# schematic.net
KiCad netlist of a schematic drawn in Altium Designer
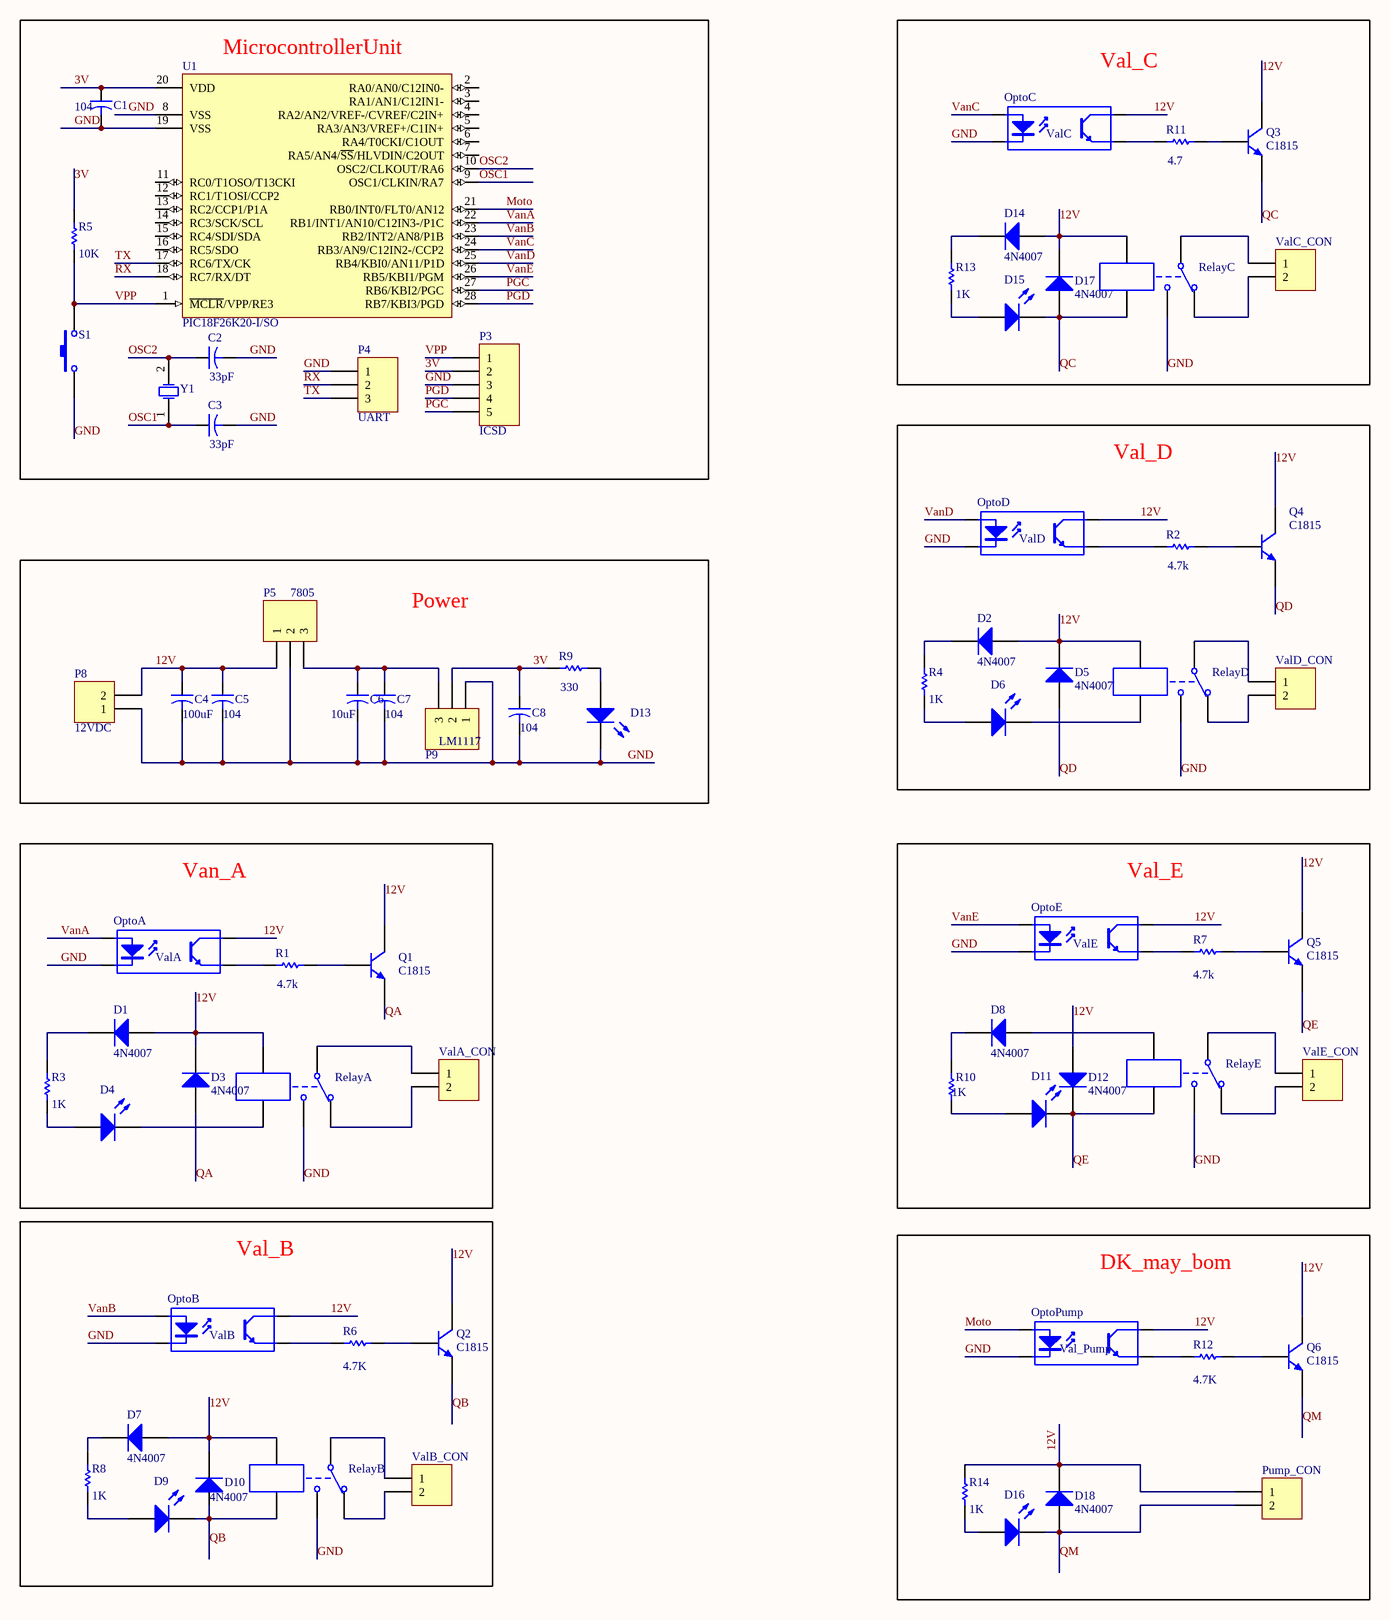
[diagram p0: schematic.SchDoc]

(export (version "E")
  (design (tool "Eeschema 10.0.6"))
  (components
    (comp (ref "C1")
      (value "104")
      (footprint "CN1")
      (description "Capacitor")
      (fields (field (name "Comment") "Cap2") (field (name "PUBLISHER") "Altium Limited"))
      (libsource (lib "Miscellaneous Devices") (part "Cap2"))
    )
    (comp (ref "C2")
      (value "33pF")
      (footprint "CN1")
      (description "Capacitor")
      (fields (field (name "Comment") "Cap2") (field (name "PUBLISHER") "Altium Limited"))
      (libsource (lib "Miscellaneous Devices") (part "Cap2"))
    )
    (comp (ref "C3")
      (value "33pF")
      (footprint "CN1")
      (description "Capacitor")
      (fields (field (name "Comment") "Cap2") (field (name "PUBLISHER") "Altium Limited"))
      (libsource (lib "Miscellaneous Devices") (part "Cap2"))
    )
    (comp (ref "C4")
      (value "100uF")
      (footprint "CP1.5/2.5")
      (description "Capacitor")
      (fields (field (name "Comment") "Cap2") (field (name "PUBLISHER") "Altium Limited"))
      (libsource (lib "Miscellaneous Devices") (part "Cap2"))
    )
    (comp (ref "C5")
      (value "104")
      (footprint "CN1")
      (description "Capacitor")
      (fields (field (name "Comment") "Cap2") (field (name "PUBLISHER") "Altium Limited"))
      (libsource (lib "Miscellaneous Devices") (part "Cap2"))
    )
    (comp (ref "C6")
      (value "10uF")
      (footprint "CP1/2")
      (description "Capacitor")
      (fields (field (name "Comment") "Cap2") (field (name "PUBLISHER") "Altium Limited"))
      (libsource (lib "Miscellaneous Devices") (part "Cap2"))
    )
    (comp (ref "C7")
      (value "104")
      (footprint "CN1")
      (description "Capacitor")
      (fields (field (name "Comment") "Cap2") (field (name "PUBLISHER") "Altium Limited"))
      (libsource (lib "Miscellaneous Devices") (part "Cap2"))
    )
    (comp (ref "C8")
      (value "104")
      (footprint "CN1")
      (description "Capacitor")
      (fields (field (name "Comment") "Cap2") (field (name "PUBLISHER") "Altium Limited"))
      (libsource (lib "Miscellaneous Devices") (part "Cap2"))
    )
    (comp (ref "D1")
      (value "4N4007")
      (footprint "D2A")
      (description "1 Amp General Purpose Rectifier")
      (fields (field (name "PUBLISHER") "Altium Limited"))
      (libsource (lib "Miscellaneous Devices") (part "Diode 1N4007"))
    )
    (comp (ref "D2")
      (value "4N4007")
      (footprint "D2A")
      (description "1 Amp General Purpose Rectifier")
      (fields (field (name "PUBLISHER") "Altium Limited"))
      (libsource (lib "Miscellaneous Devices") (part "Diode 1N4007"))
    )
    (comp (ref "D3")
      (value "4N4007")
      (footprint "D2A")
      (description "1 Amp General Purpose Rectifier")
      (fields (field (name "PUBLISHER") "Altium Limited"))
      (libsource (lib "Miscellaneous Devices") (part "Diode 1N4007"))
    )
    (comp (ref "D4")
      (value "LED1")
      (footprint "LED-5TRED")
      (description "Typical RED GaAs LED")
      (fields (field (name "PUBLISHER") "Altium Limited"))
      (libsource (lib "Miscellaneous Devices") (part "LED1"))
    )
    (comp (ref "D5")
      (value "4N4007")
      (footprint "D2A")
      (description "1 Amp General Purpose Rectifier")
      (fields (field (name "PUBLISHER") "Altium Limited"))
      (libsource (lib "Miscellaneous Devices") (part "Diode 1N4007"))
    )
    (comp (ref "D6")
      (value "LED1")
      (footprint "LED-5TRED")
      (description "Typical RED GaAs LED")
      (fields (field (name "PUBLISHER") "Altium Limited"))
      (libsource (lib "Miscellaneous Devices") (part "LED1"))
    )
    (comp (ref "D7")
      (value "4N4007")
      (footprint "D2A")
      (description "1 Amp General Purpose Rectifier")
      (fields (field (name "PUBLISHER") "Altium Limited"))
      (libsource (lib "Miscellaneous Devices") (part "Diode 1N4007"))
    )
    (comp (ref "D8")
      (value "4N4007")
      (footprint "D2A")
      (description "1 Amp General Purpose Rectifier")
      (fields (field (name "PUBLISHER") "Altium Limited"))
      (libsource (lib "Miscellaneous Devices") (part "Diode 1N4007"))
    )
    (comp (ref "D9")
      (value "LED1")
      (footprint "LED-5TRED")
      (description "Typical RED GaAs LED")
      (fields (field (name "PUBLISHER") "Altium Limited"))
      (libsource (lib "Miscellaneous Devices") (part "LED1"))
    )
    (comp (ref "D10")
      (value "4N4007")
      (footprint "D2A")
      (description "1 Amp General Purpose Rectifier")
      (fields (field (name "PUBLISHER") "Altium Limited"))
      (libsource (lib "Miscellaneous Devices") (part "Diode 1N4007"))
    )
    (comp (ref "D11")
      (value "LED1")
      (footprint "LED-5TRED")
      (description "Typical RED GaAs LED")
      (fields (field (name "PUBLISHER") "Altium Limited"))
      (libsource (lib "Miscellaneous Devices") (part "LED1"))
    )
    (comp (ref "D12")
      (value "4N4007")
      (footprint "D2A")
      (description "1 Amp General Purpose Rectifier")
      (fields (field (name "PUBLISHER") "Altium Limited"))
      (libsource (lib "Miscellaneous Devices") (part "Diode 1N4007"))
    )
    (comp (ref "D13")
      (value "LED1")
      (footprint "LED-5TRED")
      (description "Typical RED GaAs LED")
      (fields (field (name "PUBLISHER") "Altium Limited"))
      (libsource (lib "Miscellaneous Devices") (part "LED1"))
    )
    (comp (ref "D14")
      (value "4N4007")
      (footprint "D2A")
      (description "1 Amp General Purpose Rectifier")
      (fields (field (name "PUBLISHER") "Altium Limited"))
      (libsource (lib "Miscellaneous Devices") (part "Diode 1N4007"))
    )
    (comp (ref "D15")
      (value "LED1")
      (footprint "LED-5TRED")
      (description "Typical RED GaAs LED")
      (fields (field (name "PUBLISHER") "Altium Limited"))
      (libsource (lib "Miscellaneous Devices") (part "LED1"))
    )
    (comp (ref "D16")
      (value "LED1")
      (footprint "LED-5TRED")
      (description "Typical RED GaAs LED")
      (fields (field (name "PUBLISHER") "Altium Limited"))
      (libsource (lib "Miscellaneous Devices") (part "LED1"))
    )
    (comp (ref "D17")
      (value "4N4007")
      (footprint "D2A")
      (description "1 Amp General Purpose Rectifier")
      (fields (field (name "PUBLISHER") "Altium Limited"))
      (libsource (lib "Miscellaneous Devices") (part "Diode 1N4007"))
    )
    (comp (ref "D18")
      (value "4N4007")
      (footprint "D2A")
      (description "1 Amp General Purpose Rectifier")
      (fields (field (name "PUBLISHER") "Altium Limited"))
      (libsource (lib "Miscellaneous Devices") (part "Diode 1N4007"))
    )
    (comp (ref "OptoA")
      (value "ValA")
      (footprint "DIP4/W0.3")
      (description "4-Pin Phototransistor Optocoupler")
      (fields (field (name "PUBLISHER") "Altium Limited"))
      (libsource (lib "Miscellaneous Devices") (part "Optoisolator1"))
    )
    (comp (ref "OptoB")
      (value "ValB")
      (footprint "DIP4/W0.3")
      (description "4-Pin Phototransistor Optocoupler")
      (fields (field (name "PUBLISHER") "Altium Limited"))
      (libsource (lib "Miscellaneous Devices") (part "Optoisolator1"))
    )
    (comp (ref "OptoC")
      (value "ValC")
      (footprint "DIP4/W0.3")
      (description "4-Pin Phototransistor Optocoupler")
      (fields (field (name "PUBLISHER") "Altium Limited"))
      (libsource (lib "Miscellaneous Devices") (part "Optoisolator1"))
    )
    (comp (ref "OptoD")
      (value "ValD")
      (footprint "DIP4/W0.3")
      (description "4-Pin Phototransistor Optocoupler")
      (fields (field (name "PUBLISHER") "Altium Limited"))
      (libsource (lib "Miscellaneous Devices") (part "Optoisolator1"))
    )
    (comp (ref "OptoE")
      (value "ValE")
      (footprint "DIP4/W0.3")
      (description "4-Pin Phototransistor Optocoupler")
      (fields (field (name "PUBLISHER") "Altium Limited"))
      (libsource (lib "Miscellaneous Devices") (part "Optoisolator1"))
    )
    (comp (ref "OptoPump")
      (value "Val_Pump")
      (footprint "DIP4/W0.3")
      (description "4-Pin Phototransistor Optocoupler")
      (fields (field (name "PUBLISHER") "Altium Limited"))
      (libsource (lib "Miscellaneous Devices") (part "Optoisolator1"))
    )
    (comp (ref "P3")
      (value "ICSD")
      (footprint "JP5")
      (description "Header, 5-Pin, Right Angle")
      (fields (field (name "PUBLISHER") "Altium Limited"))
      (libsource (lib "Miscellaneous Connectors") (part "Header 5H"))
    )
    (comp (ref "P4")
      (value "UART")
      (footprint "JP3")
      (description "Header, 3-Pin, Right Angle")
      (fields (field (name "PUBLISHER") "Altium Limited"))
      (libsource (lib "Miscellaneous Connectors") (part "Header 3H"))
    )
    (comp (ref "P5")
      (value "7805")
      (footprint "JP3")
      (description "Header, 3-Pin, Right Angle")
      (fields (field (name "PUBLISHER") "Altium Limited"))
      (libsource (lib "") (part "Header 3H_2"))
    )
    (comp (ref "P8")
      (value "12VDC")
      (footprint "DC-IN")
      (description "Header, 2-Pin")
      (fields (field (name "PUBLISHER") "Altium Limited"))
      (libsource (lib "") (part "Header 2_1"))
    )
    (comp (ref "P9")
      (value "LM1117")
      (footprint "JP3")
      (description "Header, 3-Pin, Right Angle")
      (fields (field (name "PUBLISHER") "Altium Limited"))
      (libsource (lib "") (part "Header 3H_1"))
    )
    (comp (ref "Pump_CON")
      (value "Header 2")
      (footprint "CON2")
      (description "Header, 2-Pin")
      (fields (field (name "PUBLISHER") "Altium Limited"))
      (libsource (lib "Miscellaneous Connectors") (part "Header 2"))
    )
    (comp (ref "Q1")
      (value "C1815")
      (footprint "QTO-92")
      (description "NPN General Purpose Amplifier")
      (fields (field (name "PUBLISHER") "Altium Limited"))
      (libsource (lib "Miscellaneous Devices") (part "2N3904"))
    )
    (comp (ref "Q2")
      (value "C1815")
      (footprint "QTO-92")
      (description "NPN General Purpose Amplifier")
      (fields (field (name "PUBLISHER") "Altium Limited"))
      (libsource (lib "Miscellaneous Devices") (part "2N3904"))
    )
    (comp (ref "Q3")
      (value "C1815")
      (footprint "QTO-92")
      (description "NPN General Purpose Amplifier")
      (fields (field (name "PUBLISHER") "Altium Limited"))
      (libsource (lib "Miscellaneous Devices") (part "2N3904"))
    )
    (comp (ref "Q4")
      (value "C1815")
      (footprint "QTO-92")
      (description "NPN General Purpose Amplifier")
      (fields (field (name "PUBLISHER") "Altium Limited"))
      (libsource (lib "Miscellaneous Devices") (part "2N3904"))
    )
    (comp (ref "Q5")
      (value "C1815")
      (footprint "QTO-92")
      (description "NPN General Purpose Amplifier")
      (fields (field (name "PUBLISHER") "Altium Limited"))
      (libsource (lib "Miscellaneous Devices") (part "2N3904"))
    )
    (comp (ref "Q6")
      (value "C1815")
      (footprint "QTO-92")
      (description "NPN General Purpose Amplifier")
      (fields (field (name "PUBLISHER") "Altium Limited"))
      (libsource (lib "Miscellaneous Devices") (part "2N3904"))
    )
    (comp (ref "R1")
      (value "4.7k")
      (footprint "R1/4W")
      (description "Resistor")
      (fields (field (name "Comment") "Res1") (field (name "PUBLISHER") "Altium Limited"))
      (libsource (lib "Miscellaneous Devices") (part "Res1"))
    )
    (comp (ref "R2")
      (value "4.7k")
      (footprint "R1/4W")
      (description "Resistor")
      (fields (field (name "PUBLISHER") "Altium Limited"))
      (libsource (lib "Miscellaneous Devices") (part "Res1"))
    )
    (comp (ref "R3")
      (value "1K")
      (footprint "R1/4W")
      (description "Resistor")
      (fields (field (name "Comment") "Res1") (field (name "PUBLISHER") "Altium Limited"))
      (libsource (lib "Miscellaneous Devices") (part "Res1"))
    )
    (comp (ref "R4")
      (value "1K")
      (footprint "R1/4W")
      (description "Resistor")
      (fields (field (name "Comment") "Res1") (field (name "PUBLISHER") "Altium Limited"))
      (libsource (lib "Miscellaneous Devices") (part "Res1"))
    )
    (comp (ref "R5")
      (value "10K")
      (footprint "R1/4W")
      (description "Resistor")
      (fields (field (name "Comment") "Res1") (field (name "PUBLISHER") "Altium Limited"))
      (libsource (lib "Miscellaneous Devices") (part "Res1"))
    )
    (comp (ref "R6")
      (value "4.7K")
      (footprint "R1/4W")
      (description "Resistor")
      (fields (field (name "Comment") "Res1") (field (name "PUBLISHER") "Altium Limited"))
      (libsource (lib "Miscellaneous Devices") (part "Res1"))
    )
    (comp (ref "R7")
      (value "4.7k")
      (footprint "R1/4W")
      (description "Resistor")
      (fields (field (name "Comment") "Res1") (field (name "PUBLISHER") "Altium Limited"))
      (libsource (lib "Miscellaneous Devices") (part "Res1"))
    )
    (comp (ref "R8")
      (value "1K")
      (footprint "R1/4W")
      (description "Resistor")
      (fields (field (name "Comment") "Res1") (field (name "PUBLISHER") "Altium Limited"))
      (libsource (lib "Miscellaneous Devices") (part "Res1"))
    )
    (comp (ref "R9")
      (value "330")
      (footprint "R1/4W")
      (description "Resistor")
      (fields (field (name "Comment") "Res1") (field (name "PUBLISHER") "Altium Limited"))
      (libsource (lib "Miscellaneous Devices") (part "Res1"))
    )
    (comp (ref "R10")
      (value "1K")
      (footprint "R1/4W")
      (description "Resistor")
      (fields (field (name "Comment") "Res1") (field (name "PUBLISHER") "Altium Limited"))
      (libsource (lib "Miscellaneous Devices") (part "Res1"))
    )
    (comp (ref "R11")
      (value "4.7")
      (footprint "R1/4W")
      (description "Resistor")
      (fields (field (name "Comment") "Res1") (field (name "PUBLISHER") "Altium Limited"))
      (libsource (lib "Miscellaneous Devices") (part "Res1"))
    )
    (comp (ref "R12")
      (value "4.7K")
      (footprint "R1/4W")
      (description "Resistor")
      (fields (field (name "Comment") "Res1") (field (name "PUBLISHER") "Altium Limited"))
      (libsource (lib "Miscellaneous Devices") (part "Res1"))
    )
    (comp (ref "R13")
      (value "1K")
      (footprint "R1/4W")
      (description "Resistor")
      (fields (field (name "Comment") "Res1") (field (name "PUBLISHER") "Altium Limited"))
      (libsource (lib "Miscellaneous Devices") (part "Res1"))
    )
    (comp (ref "R14")
      (value "1K")
      (footprint "R1/4W")
      (description "Resistor")
      (fields (field (name "Comment") "Res1") (field (name "PUBLISHER") "Altium Limited"))
      (libsource (lib "Miscellaneous Devices") (part "Res1"))
    )
    (comp (ref "RelayA")
      (value "Relay-SPDT")
      (footprint "RL_SPDT_10A")
      (description "Single-Pole Dual-Throw Relay")
      (fields (field (name "PUBLISHER") "Altium Limited"))
      (libsource (lib "Miscellaneous Devices") (part "Relay-SPDT"))
    )
    (comp (ref "RelayB")
      (value "Relay-SPDT")
      (footprint "RL_SPDT_10A")
      (description "Single-Pole Dual-Throw Relay")
      (fields (field (name "PUBLISHER") "Altium Limited"))
      (libsource (lib "Miscellaneous Devices") (part "Relay-SPDT"))
    )
    (comp (ref "RelayC")
      (value "Relay-SPDT")
      (footprint "RL_SPDT_10A")
      (description "Single-Pole Dual-Throw Relay")
      (fields (field (name "PUBLISHER") "Altium Limited"))
      (libsource (lib "Miscellaneous Devices") (part "Relay-SPDT"))
    )
    (comp (ref "RelayD")
      (value "Relay-SPDT")
      (footprint "RL_SPDT_10A")
      (description "Single-Pole Dual-Throw Relay")
      (fields (field (name "PUBLISHER") "Altium Limited"))
      (libsource (lib "Miscellaneous Devices") (part "Relay-SPDT"))
    )
    (comp (ref "RelayE")
      (value "Relay-SPDT")
      (footprint "RL_SPDT_10A")
      (description "Single-Pole Dual-Throw Relay")
      (fields (field (name "PUBLISHER") "Altium Limited"))
      (libsource (lib "Miscellaneous Devices") (part "Relay-SPDT"))
    )
    (comp (ref "S1")
      (value "SW-PB")
      (footprint "SW2")
      (description "Switch")
      (fields (field (name "PUBLISHER") "Altium Limited"))
      (libsource (lib "Miscellaneous Devices") (part "SW-PB"))
    )
    (comp (ref "U1")
      (value "PIC18F26K20-I/SO")
      (footprint "SOP_28M_127")
      (fields (field (name "PUBLISHER") "Altium Limited"))
      (libsource (lib "Microchip Microcontroller 8-Bit PIC18") (part "PIC18F26K20-I/SO"))
    )
    (comp (ref "ValA_CON")
      (value "Header 2")
      (footprint "CON2")
      (description "Header, 2-Pin")
      (fields (field (name "PUBLISHER") "Altium Limited"))
      (libsource (lib "Miscellaneous Connectors") (part "Header 2"))
    )
    (comp (ref "ValB_CON")
      (value "Header 2")
      (footprint "CON2")
      (description "Header, 2-Pin")
      (fields (field (name "PUBLISHER") "Altium Limited"))
      (libsource (lib "Miscellaneous Connectors") (part "Header 2"))
    )
    (comp (ref "ValC_CON")
      (value "Header 2")
      (footprint "CON2")
      (description "Header, 2-Pin")
      (fields (field (name "PUBLISHER") "Altium Limited"))
      (libsource (lib "Miscellaneous Connectors") (part "Header 2"))
    )
    (comp (ref "ValD_CON")
      (value "Header 2")
      (footprint "CON2")
      (description "Header, 2-Pin")
      (fields (field (name "PUBLISHER") "Altium Limited"))
      (libsource (lib "Miscellaneous Connectors") (part "Header 2"))
    )
    (comp (ref "ValE_CON")
      (value "Header 2")
      (footprint "CON2")
      (description "Header, 2-Pin")
      (fields (field (name "PUBLISHER") "Altium Limited"))
      (libsource (lib "Miscellaneous Connectors") (part "Header 2"))
    )
    (comp (ref "Y1")
      (value "8Mhz")
      (footprint "XT2")
      (description "Crystal Oscillator")
      (fields (field (name "PUBLISHER") "Altium Limited"))
      (libsource (lib "Miscellaneous Devices") (part "XTAL"))
    )
  )
  (nets
    (net (code "1") (name "/3V") (class "Default")
      (node (ref "C1") (pin "1") (pinfunction "1_1") (pintype "passive"))
      (node (ref "C8") (pin "1") (pinfunction "1_1") (pintype "passive"))
      (node (ref "P3") (pin "2") (pinfunction "2_2") (pintype "passive"))
      (node (ref "P9") (pin "2") (pinfunction "2_2") (pintype "passive"))
      (node (ref "R5") (pin "2") (pinfunction "2_2") (pintype "passive"))
      (node (ref "R9") (pin "1") (pinfunction "1_1") (pintype "passive"))
      (node (ref "U1") (pin "20") (pinfunction "VDD_20") (pintype "power_in"))
    )
    (net (code "2") (name "/12V") (class "Default")
      (node (ref "C4") (pin "1") (pinfunction "1_1") (pintype "passive"))
      (node (ref "C5") (pin "1") (pinfunction "1_1") (pintype "passive"))
      (node (ref "D1") (pin "1") (pinfunction "A_1") (pintype "passive"))
      (node (ref "D10") (pin "2") (pinfunction "K_2") (pintype "passive"))
      (node (ref "D12") (pin "1") (pinfunction "A_1") (pintype "passive"))
      (node (ref "D14") (pin "1") (pinfunction "A_1") (pintype "passive"))
      (node (ref "D17") (pin "2") (pinfunction "K_2") (pintype "passive"))
      (node (ref "D18") (pin "2") (pinfunction "K_2") (pintype "passive"))
      (node (ref "D2") (pin "1") (pinfunction "A_1") (pintype "passive"))
      (node (ref "D3") (pin "2") (pinfunction "K_2") (pintype "passive"))
      (node (ref "D5") (pin "2") (pinfunction "K_2") (pintype "passive"))
      (node (ref "D7") (pin "1") (pinfunction "A_1") (pintype "passive"))
      (node (ref "OptoA") (pin "4") (pinfunction "C_4") (pintype "passive"))
      (node (ref "OptoB") (pin "4") (pinfunction "C_4") (pintype "passive"))
      (node (ref "OptoC") (pin "4") (pinfunction "C_4") (pintype "passive"))
      (node (ref "OptoD") (pin "4") (pinfunction "C_4") (pintype "passive"))
      (node (ref "OptoE") (pin "4") (pinfunction "C_4") (pintype "passive"))
      (node (ref "OptoPump") (pin "4") (pinfunction "C_4") (pintype "passive"))
      (node (ref "P5") (pin "1") (pinfunction "1_1") (pintype "passive"))
      (node (ref "P8") (pin "2") (pinfunction "2_2") (pintype "passive"))
      (node (ref "Pump_CON") (pin "1") (pinfunction "1_1") (pintype "passive"))
      (node (ref "Q1") (pin "3") (pinfunction "C_3") (pintype "passive"))
      (node (ref "Q2") (pin "3") (pinfunction "C_3") (pintype "passive"))
      (node (ref "Q3") (pin "3") (pinfunction "C_3") (pintype "passive"))
      (node (ref "Q4") (pin "3") (pinfunction "C_3") (pintype "passive"))
      (node (ref "Q5") (pin "3") (pinfunction "C_3") (pintype "passive"))
      (node (ref "Q6") (pin "3") (pinfunction "C_3") (pintype "passive"))
      (node (ref "R14") (pin "1") (pinfunction "1_1") (pintype "passive"))
      (node (ref "RelayA") (pin "4") (pinfunction "4_4") (pintype "passive"))
      (node (ref "RelayB") (pin "4") (pinfunction "4_4") (pintype "passive"))
      (node (ref "RelayC") (pin "4") (pinfunction "4_4") (pintype "passive"))
      (node (ref "RelayD") (pin "4") (pinfunction "4_4") (pintype "passive"))
    )
    (net (code "3") (name "/GND") (class "Default")
      (node (ref "C1") (pin "2") (pinfunction "2_2") (pintype "passive"))
      (node (ref "C2") (pin "2") (pinfunction "2_2") (pintype "passive"))
      (node (ref "C3") (pin "2") (pinfunction "2_2") (pintype "passive"))
      (node (ref "C4") (pin "2") (pinfunction "2_2") (pintype "passive"))
      (node (ref "C5") (pin "2") (pinfunction "2_2") (pintype "passive"))
      (node (ref "C6") (pin "2") (pinfunction "2_2") (pintype "passive"))
      (node (ref "C7") (pin "2") (pinfunction "2_2") (pintype "passive"))
      (node (ref "C8") (pin "2") (pinfunction "2_2") (pintype "passive"))
      (node (ref "D13") (pin "2") (pinfunction "K_2") (pintype "passive"))
      (node (ref "OptoA") (pin "2") (pinfunction "K_2") (pintype "passive"))
      (node (ref "OptoB") (pin "2") (pinfunction "K_2") (pintype "passive"))
      (node (ref "OptoC") (pin "2") (pinfunction "K_2") (pintype "passive"))
      (node (ref "OptoD") (pin "2") (pinfunction "K_2") (pintype "passive"))
      (node (ref "OptoE") (pin "2") (pinfunction "K_2") (pintype "passive"))
      (node (ref "OptoPump") (pin "2") (pinfunction "K_2") (pintype "passive"))
      (node (ref "P3") (pin "3") (pinfunction "3_3") (pintype "passive"))
      (node (ref "P4") (pin "1") (pinfunction "1_1") (pintype "passive"))
      (node (ref "P5") (pin "2") (pinfunction "2_2") (pintype "passive"))
      (node (ref "P8") (pin "1") (pinfunction "1_1") (pintype "passive"))
      (node (ref "P9") (pin "1") (pinfunction "1_1") (pintype "passive"))
      (node (ref "RelayA") (pin "3") (pinfunction "3_3") (pintype "passive"))
      (node (ref "RelayB") (pin "3") (pinfunction "3_3") (pintype "passive"))
      (node (ref "RelayC") (pin "3") (pinfunction "3_3") (pintype "passive"))
      (node (ref "RelayD") (pin "3") (pinfunction "3_3") (pintype "passive"))
      (node (ref "RelayE") (pin "3") (pinfunction "3_3") (pintype "passive"))
      (node (ref "S1") (pin "1") (pinfunction "1_1") (pintype "passive"))
      (node (ref "U1") (pin "19") (pinfunction "VSS_19") (pintype "power_in"))
      (node (ref "U1") (pin "8") (pinfunction "VSS_8") (pintype "power_in"))
    )
    (net (code "4") (name "/Moto") (class "Default")
      (node (ref "OptoPump") (pin "1") (pinfunction "A_1") (pintype "passive"))
      (node (ref "U1") (pin "21") (pinfunction "RB0/INT0/FLT0/AN12_21") (pintype "bidirectional"))
    )
    (net (code "5") (name "/OSC1") (class "Default")
      (node (ref "C3") (pin "1") (pinfunction "1_1") (pintype "passive"))
      (node (ref "U1") (pin "9") (pinfunction "OSC1/CLKIN/RA7_9") (pintype "bidirectional"))
      (node (ref "Y1") (pin "1") (pinfunction "OSC1_1") (pintype "passive"))
    )
    (net (code "6") (name "/OSC2") (class "Default")
      (node (ref "C2") (pin "1") (pinfunction "1_1") (pintype "passive"))
      (node (ref "U1") (pin "10") (pinfunction "OSC2/CLKOUT/RA6_10") (pintype "bidirectional"))
      (node (ref "Y1") (pin "2") (pinfunction "OSC2_2") (pintype "passive"))
    )
    (net (code "7") (name "/PGC") (class "Default")
      (node (ref "P3") (pin "5") (pinfunction "5_5") (pintype "passive"))
      (node (ref "U1") (pin "27") (pinfunction "RB6/KBI2/PGC_27") (pintype "bidirectional"))
    )
    (net (code "8") (name "/PGD") (class "Default")
      (node (ref "P3") (pin "4") (pinfunction "4_4") (pintype "passive"))
      (node (ref "U1") (pin "28") (pinfunction "RB7/KBI3/PGD_28") (pintype "bidirectional"))
    )
    (net (code "9") (name "/QA") (class "Default")
      (node (ref "D3") (pin "1") (pinfunction "A_1") (pintype "passive"))
      (node (ref "Q1") (pin "1") (pinfunction "E_1") (pintype "passive"))
    )
    (net (code "10") (name "/QB") (class "Default")
      (node (ref "D10") (pin "1") (pinfunction "A_1") (pintype "passive"))
      (node (ref "D9") (pin "2") (pinfunction "K_2") (pintype "passive"))
      (node (ref "Q2") (pin "1") (pinfunction "E_1") (pintype "passive"))
      (node (ref "RelayB") (pin "5") (pinfunction "5_5") (pintype "passive"))
    )
    (net (code "11") (name "/QC") (class "Default")
      (node (ref "D15") (pin "2") (pinfunction "K_2") (pintype "passive"))
      (node (ref "D17") (pin "1") (pinfunction "A_1") (pintype "passive"))
      (node (ref "Q3") (pin "1") (pinfunction "E_1") (pintype "passive"))
      (node (ref "RelayC") (pin "5") (pinfunction "5_5") (pintype "passive"))
    )
    (net (code "12") (name "/QD") (class "Default")
      (node (ref "D5") (pin "1") (pinfunction "A_1") (pintype "passive"))
      (node (ref "Q4") (pin "1") (pinfunction "E_1") (pintype "passive"))
    )
    (net (code "13") (name "/QE") (class "Default")
      (node (ref "D11") (pin "2") (pinfunction "K_2") (pintype "passive"))
      (node (ref "D12") (pin "2") (pinfunction "K_2") (pintype "passive"))
      (node (ref "Q5") (pin "1") (pinfunction "E_1") (pintype "passive"))
      (node (ref "RelayE") (pin "5") (pinfunction "5_5") (pintype "passive"))
    )
    (net (code "14") (name "/QM") (class "Default")
      (node (ref "D16") (pin "2") (pinfunction "K_2") (pintype "passive"))
      (node (ref "D18") (pin "1") (pinfunction "A_1") (pintype "passive"))
      (node (ref "Pump_CON") (pin "2") (pinfunction "2_2") (pintype "passive"))
      (node (ref "Q6") (pin "1") (pinfunction "E_1") (pintype "passive"))
    )
    (net (code "15") (name "/RX") (class "Default")
      (node (ref "P4") (pin "2") (pinfunction "2_2") (pintype "passive"))
      (node (ref "U1") (pin "18") (pinfunction "RC7/RX/DT_18") (pintype "bidirectional"))
    )
    (net (code "16") (name "/TX") (class "Default")
      (node (ref "P4") (pin "3") (pinfunction "3_3") (pintype "passive"))
      (node (ref "U1") (pin "17") (pinfunction "RC6/TX/CK_17") (pintype "bidirectional"))
    )
    (net (code "17") (name "/VPP") (class "Default")
      (node (ref "P3") (pin "1") (pinfunction "1_1") (pintype "passive"))
      (node (ref "R5") (pin "1") (pinfunction "1_1") (pintype "passive"))
      (node (ref "S1") (pin "2") (pinfunction "2_2") (pintype "passive"))
      (node (ref "U1") (pin "1") (pinfunction "~{MCLR}/VPP/RE3_1") (pintype "input"))
    )
    (net (code "18") (name "/VanA") (class "Default")
      (node (ref "OptoA") (pin "1") (pinfunction "A_1") (pintype "passive"))
      (node (ref "U1") (pin "22") (pinfunction "RB1/INT1/AN10/C12IN3-/P1C_22") (pintype "bidirectional"))
    )
    (net (code "19") (name "/VanB") (class "Default")
      (node (ref "OptoB") (pin "1") (pinfunction "A_1") (pintype "passive"))
      (node (ref "U1") (pin "23") (pinfunction "RB2/INT2/AN8/P1B_23") (pintype "bidirectional"))
    )
    (net (code "20") (name "/VanC") (class "Default")
      (node (ref "OptoC") (pin "1") (pinfunction "A_1") (pintype "passive"))
      (node (ref "U1") (pin "24") (pinfunction "RB3/AN9/C12IN2-/CCP2_24") (pintype "bidirectional"))
    )
    (net (code "21") (name "/VanD") (class "Default")
      (node (ref "OptoD") (pin "1") (pinfunction "A_1") (pintype "passive"))
      (node (ref "U1") (pin "25") (pinfunction "RB4/KBI0/AN11/P1D_25") (pintype "bidirectional"))
    )
    (net (code "22") (name "/VanE") (class "Default")
      (node (ref "OptoE") (pin "1") (pinfunction "A_1") (pintype "passive"))
      (node (ref "U1") (pin "26") (pinfunction "RB5/KBI1/PGM_26") (pintype "bidirectional"))
    )
    (net (code "23") (name "Net-(C6-Pad1)") (class "Default")
      (node (ref "C6") (pin "1") (pinfunction "1_1") (pintype "passive"))
      (node (ref "C7") (pin "1") (pinfunction "1_1") (pintype "passive"))
      (node (ref "P5") (pin "3") (pinfunction "3_3") (pintype "passive"))
      (node (ref "P9") (pin "3") (pinfunction "3_3") (pintype "passive"))
    )
    (net (code "24") (name "Net-(D1-K)") (class "Default")
      (node (ref "D1") (pin "2") (pinfunction "K_2") (pintype "passive"))
      (node (ref "R3") (pin "1") (pinfunction "1_1") (pintype "passive"))
    )
    (net (code "25") (name "Net-(D2-K)") (class "Default")
      (node (ref "D2") (pin "2") (pinfunction "K_2") (pintype "passive"))
      (node (ref "R4") (pin "1") (pinfunction "1_1") (pintype "passive"))
    )
    (net (code "26") (name "Net-(D4-A)") (class "Default")
      (node (ref "D4") (pin "1") (pinfunction "A_1") (pintype "passive"))
      (node (ref "R3") (pin "2") (pinfunction "2_2") (pintype "passive"))
    )
    (net (code "27") (name "Net-(D4-K)") (class "Default")
      (node (ref "D4") (pin "2") (pinfunction "K_2") (pintype "passive"))
      (node (ref "RelayA") (pin "5") (pinfunction "5_5") (pintype "passive"))
    )
    (net (code "28") (name "Net-(D6-A)") (class "Default")
      (node (ref "D6") (pin "1") (pinfunction "A_1") (pintype "passive"))
      (node (ref "R4") (pin "2") (pinfunction "2_2") (pintype "passive"))
    )
    (net (code "29") (name "Net-(D6-K)") (class "Default")
      (node (ref "D6") (pin "2") (pinfunction "K_2") (pintype "passive"))
      (node (ref "RelayD") (pin "5") (pinfunction "5_5") (pintype "passive"))
    )
    (net (code "30") (name "Net-(D7-K)") (class "Default")
      (node (ref "D7") (pin "2") (pinfunction "K_2") (pintype "passive"))
      (node (ref "R8") (pin "1") (pinfunction "1_1") (pintype "passive"))
    )
    (net (code "31") (name "Net-(D8-A)") (class "Default")
      (node (ref "D8") (pin "1") (pinfunction "A_1") (pintype "passive"))
      (node (ref "RelayE") (pin "4") (pinfunction "4_4") (pintype "passive"))
    )
    (net (code "32") (name "Net-(D8-K)") (class "Default")
      (node (ref "D8") (pin "2") (pinfunction "K_2") (pintype "passive"))
      (node (ref "R10") (pin "1") (pinfunction "1_1") (pintype "passive"))
    )
    (net (code "33") (name "Net-(D9-A)") (class "Default")
      (node (ref "D9") (pin "1") (pinfunction "A_1") (pintype "passive"))
      (node (ref "R8") (pin "2") (pinfunction "2_2") (pintype "passive"))
    )
    (net (code "34") (name "Net-(D11-A)") (class "Default")
      (node (ref "D11") (pin "1") (pinfunction "A_1") (pintype "passive"))
      (node (ref "R10") (pin "2") (pinfunction "2_2") (pintype "passive"))
    )
    (net (code "35") (name "Net-(D13-A)") (class "Default")
      (node (ref "D13") (pin "1") (pinfunction "A_1") (pintype "passive"))
      (node (ref "R9") (pin "2") (pinfunction "2_2") (pintype "passive"))
    )
    (net (code "36") (name "Net-(D14-K)") (class "Default")
      (node (ref "D14") (pin "2") (pinfunction "K_2") (pintype "passive"))
      (node (ref "R13") (pin "1") (pinfunction "1_1") (pintype "passive"))
    )
    (net (code "37") (name "Net-(D15-A)") (class "Default")
      (node (ref "D15") (pin "1") (pinfunction "A_1") (pintype "passive"))
      (node (ref "R13") (pin "2") (pinfunction "2_2") (pintype "passive"))
    )
    (net (code "38") (name "Net-(D16-A)") (class "Default")
      (node (ref "D16") (pin "1") (pinfunction "A_1") (pintype "passive"))
      (node (ref "R14") (pin "2") (pinfunction "2_2") (pintype "passive"))
    )
    (net (code "39") (name "Net-(OptoA-E)") (class "Default")
      (node (ref "OptoA") (pin "3") (pinfunction "E_3") (pintype "passive"))
      (node (ref "R1") (pin "1") (pinfunction "1_1") (pintype "passive"))
    )
    (net (code "40") (name "Net-(OptoB-E)") (class "Default")
      (node (ref "OptoB") (pin "3") (pinfunction "E_3") (pintype "passive"))
      (node (ref "R6") (pin "1") (pinfunction "1_1") (pintype "passive"))
    )
    (net (code "41") (name "Net-(OptoC-E)") (class "Default")
      (node (ref "OptoC") (pin "3") (pinfunction "E_3") (pintype "passive"))
      (node (ref "R11") (pin "1") (pinfunction "1_1") (pintype "passive"))
    )
    (net (code "42") (name "Net-(OptoD-E)") (class "Default")
      (node (ref "OptoD") (pin "3") (pinfunction "E_3") (pintype "passive"))
      (node (ref "R2") (pin "1") (pinfunction "1_1") (pintype "passive"))
    )
    (net (code "43") (name "Net-(OptoE-E)") (class "Default")
      (node (ref "OptoE") (pin "3") (pinfunction "E_3") (pintype "passive"))
      (node (ref "R7") (pin "1") (pinfunction "1_1") (pintype "passive"))
    )
    (net (code "44") (name "Net-(OptoPump-E)") (class "Default")
      (node (ref "OptoPump") (pin "3") (pinfunction "E_3") (pintype "passive"))
      (node (ref "R12") (pin "1") (pinfunction "1_1") (pintype "passive"))
    )
    (net (code "45") (name "Net-(Q1-B)") (class "Default")
      (node (ref "Q1") (pin "2") (pinfunction "B_2") (pintype "passive"))
      (node (ref "R1") (pin "2") (pinfunction "2_2") (pintype "passive"))
    )
    (net (code "46") (name "Net-(Q2-B)") (class "Default")
      (node (ref "Q2") (pin "2") (pinfunction "B_2") (pintype "passive"))
      (node (ref "R6") (pin "2") (pinfunction "2_2") (pintype "passive"))
    )
    (net (code "47") (name "Net-(Q3-B)") (class "Default")
      (node (ref "Q3") (pin "2") (pinfunction "B_2") (pintype "passive"))
      (node (ref "R11") (pin "2") (pinfunction "2_2") (pintype "passive"))
    )
    (net (code "48") (name "Net-(Q4-B)") (class "Default")
      (node (ref "Q4") (pin "2") (pinfunction "B_2") (pintype "passive"))
      (node (ref "R2") (pin "2") (pinfunction "2_2") (pintype "passive"))
    )
    (net (code "49") (name "Net-(Q5-B)") (class "Default")
      (node (ref "Q5") (pin "2") (pinfunction "B_2") (pintype "passive"))
      (node (ref "R7") (pin "2") (pinfunction "2_2") (pintype "passive"))
    )
    (net (code "50") (name "Net-(Q6-B)") (class "Default")
      (node (ref "Q6") (pin "2") (pinfunction "B_2") (pintype "passive"))
      (node (ref "R12") (pin "2") (pinfunction "2_2") (pintype "passive"))
    )
    (net (code "51") (name "Net-(RelayA-Pad1)") (class "Default")
      (node (ref "RelayA") (pin "1") (pinfunction "1_1") (pintype "passive"))
      (node (ref "ValA_CON") (pin "1") (pinfunction "1_1") (pintype "passive"))
    )
    (net (code "52") (name "Net-(RelayA-Pad2)") (class "Default")
      (node (ref "RelayA") (pin "2") (pinfunction "2_2") (pintype "passive"))
      (node (ref "ValA_CON") (pin "2") (pinfunction "2_2") (pintype "passive"))
    )
    (net (code "53") (name "Net-(RelayB-Pad1)") (class "Default")
      (node (ref "RelayB") (pin "1") (pinfunction "1_1") (pintype "passive"))
      (node (ref "ValB_CON") (pin "1") (pinfunction "1_1") (pintype "passive"))
    )
    (net (code "54") (name "Net-(RelayB-Pad2)") (class "Default")
      (node (ref "RelayB") (pin "2") (pinfunction "2_2") (pintype "passive"))
      (node (ref "ValB_CON") (pin "2") (pinfunction "2_2") (pintype "passive"))
    )
    (net (code "55") (name "Net-(RelayC-Pad1)") (class "Default")
      (node (ref "RelayC") (pin "1") (pinfunction "1_1") (pintype "passive"))
      (node (ref "ValC_CON") (pin "1") (pinfunction "1_1") (pintype "passive"))
    )
    (net (code "56") (name "Net-(RelayC-Pad2)") (class "Default")
      (node (ref "RelayC") (pin "2") (pinfunction "2_2") (pintype "passive"))
      (node (ref "ValC_CON") (pin "2") (pinfunction "2_2") (pintype "passive"))
    )
    (net (code "57") (name "Net-(RelayD-Pad1)") (class "Default")
      (node (ref "RelayD") (pin "1") (pinfunction "1_1") (pintype "passive"))
      (node (ref "ValD_CON") (pin "1") (pinfunction "1_1") (pintype "passive"))
    )
    (net (code "58") (name "Net-(RelayD-Pad2)") (class "Default")
      (node (ref "RelayD") (pin "2") (pinfunction "2_2") (pintype "passive"))
      (node (ref "ValD_CON") (pin "2") (pinfunction "2_2") (pintype "passive"))
    )
    (net (code "59") (name "Net-(RelayE-Pad1)") (class "Default")
      (node (ref "RelayE") (pin "1") (pinfunction "1_1") (pintype "passive"))
      (node (ref "ValE_CON") (pin "1") (pinfunction "1_1") (pintype "passive"))
    )
    (net (code "60") (name "Net-(RelayE-Pad2)") (class "Default")
      (node (ref "RelayE") (pin "2") (pinfunction "2_2") (pintype "passive"))
      (node (ref "ValE_CON") (pin "2") (pinfunction "2_2") (pintype "passive"))
    )
    (net (code "61") (name "unconnected-(U1-RA0{slash}AN0{slash}C12IN0--Pad2)") (class "Default")
      (node (ref "U1") (pin "2") (pinfunction "RA0/AN0/C12IN0-_2") (pintype "bidirectional"))
    )
    (net (code "62") (name "unconnected-(U1-RA1{slash}AN1{slash}C12IN1--Pad3)") (class "Default")
      (node (ref "U1") (pin "3") (pinfunction "RA1/AN1/C12IN1-_3") (pintype "bidirectional"))
    )
    (net (code "63") (name "unconnected-(U1-RA2{slash}AN2{slash}VREF-{slash}CVREF{slash}C2IN+-Pad4)") (class "Default")
      (node (ref "U1") (pin "4") (pinfunction "RA2/AN2/VREF-/CVREF/C2IN+_4") (pintype "bidirectional"))
    )
    (net (code "64") (name "unconnected-(U1-RA3{slash}AN3{slash}VREF+{slash}C1IN+-Pad5)") (class "Default")
      (node (ref "U1") (pin "5") (pinfunction "RA3/AN3/VREF+/C1IN+_5") (pintype "bidirectional"))
    )
    (net (code "65") (name "unconnected-(U1-RA4{slash}T0CKI{slash}C1OUT-Pad6)") (class "Default")
      (node (ref "U1") (pin "6") (pinfunction "RA4/T0CKI/C1OUT_6") (pintype "bidirectional"))
    )
    (net (code "66") (name "unconnected-(U1-RA5{slash}AN4{slash}~{SS}{slash}HLVDIN{slash}C2OUT-Pad7)") (class "Default")
      (node (ref "U1") (pin "7") (pinfunction "RA5/AN4/~{SS}/HLVDIN/C2OUT_7") (pintype "bidirectional"))
    )
    (net (code "67") (name "unconnected-(U1-RC0{slash}T1OSO{slash}T13CKI-Pad11)") (class "Default")
      (node (ref "U1") (pin "11") (pinfunction "RC0/T1OSO/T13CKI_11") (pintype "bidirectional"))
    )
    (net (code "68") (name "unconnected-(U1-RC1{slash}T1OSI{slash}CCP2-Pad12)") (class "Default")
      (node (ref "U1") (pin "12") (pinfunction "RC1/T1OSI/CCP2_12") (pintype "bidirectional"))
    )
    (net (code "69") (name "unconnected-(U1-RC2{slash}CCP1{slash}P1A-Pad13)") (class "Default")
      (node (ref "U1") (pin "13") (pinfunction "RC2/CCP1/P1A_13") (pintype "bidirectional"))
    )
    (net (code "70") (name "unconnected-(U1-RC3{slash}SCK{slash}SCL-Pad14)") (class "Default")
      (node (ref "U1") (pin "14") (pinfunction "RC3/SCK/SCL_14") (pintype "bidirectional"))
    )
    (net (code "71") (name "unconnected-(U1-RC4{slash}SDI{slash}SDA-Pad15)") (class "Default")
      (node (ref "U1") (pin "15") (pinfunction "RC4/SDI/SDA_15") (pintype "bidirectional"))
    )
    (net (code "72") (name "unconnected-(U1-RC5{slash}SDO-Pad16)") (class "Default")
      (node (ref "U1") (pin "16") (pinfunction "RC5/SDO_16") (pintype "bidirectional"))
    )
  )
)
